# Proyecto_etapa_1_y_2.net
KiCad netlist of a schematic drawn in EAGLE
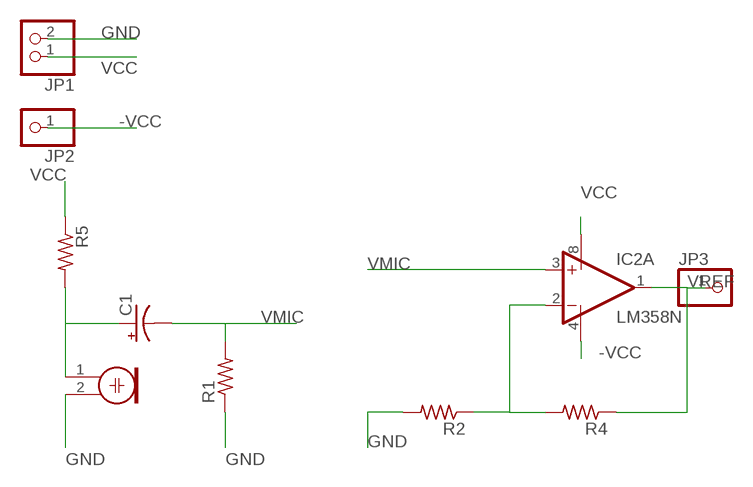
[diagram p0: schematic, sheet 1]

(export (version "E")
  (design (tool "Eeschema 10.0.6"))
  (components
    (comp (ref "C1")
      (value "CPOL-USE2.5-6")
      (footprint "eagle-import:E2,5-6")
      (libsource (lib "eagle-import") (part "CPOL-USE2.5-6"))
    )
    (comp (ref "IC2")
      (value "LM358N")
      (footprint "eagle-import:DIL08")
      (libsource (lib "eagle-import") (part "LM358N"))
    )
    (comp (ref "JP1")
      (value "PINHD-1X2")
      (footprint "eagle-import:1X02")
      (libsource (lib "eagle-import") (part "PINHD-1X2"))
    )
    (comp (ref "JP2")
      (value "PINHD-1X1")
      (footprint "eagle-import:1X01")
      (libsource (lib "eagle-import") (part "PINHD-1X1"))
    )
    (comp (ref "JP3")
      (value "PINHD-1X1")
      (footprint "eagle-import:1X01")
      (libsource (lib "eagle-import") (part "PINHD-1X1"))
    )
    (comp (ref "M2")
      (value "ELECTRET_MICROPHON-F6050AP")
      (footprint "eagle-import:F6050AP")
      (libsource (lib "eagle-import") (part "ELECTRET_MICROPHON-F6050AP"))
    )
    (comp (ref "R1")
      (value "R-US_0207/10")
      (footprint "eagle-import:0207_10")
      (libsource (lib "eagle-import") (part "R-US_0207/10"))
    )
    (comp (ref "R2")
      (value "R-US_0207/10")
      (footprint "eagle-import:0207_10")
      (libsource (lib "eagle-import") (part "R-US_0207/10"))
    )
    (comp (ref "R4")
      (value "R-US_0207/10")
      (footprint "eagle-import:0207_10")
      (libsource (lib "eagle-import") (part "R-US_0207/10"))
    )
    (comp (ref "R5")
      (value "R-US_0207/10")
      (footprint "eagle-import:0207_10")
      (libsource (lib "eagle-import") (part "R-US_0207/10"))
    )
  )
  (nets
    (net (code "1") (name "/-VCC") (class "Default")
      (node (ref "IC2") (pin "4") (pinfunction "V-_4") (pintype "power_in"))
      (node (ref "JP2") (pin "1") (pinfunction "1_1") (pintype "passive"))
    )
    (net (code "2") (name "/GND") (class "Default")
      (node (ref "JP1") (pin "2") (pinfunction "2_2") (pintype "passive"))
      (node (ref "M2") (pin "2") (pinfunction "2_2") (pintype "passive"))
      (node (ref "R1") (pin "1") (pinfunction "1_1") (pintype "passive"))
      (node (ref "R2") (pin "2") (pinfunction "2_2") (pintype "passive"))
    )
    (net (code "3") (name "/VCC") (class "Default")
      (node (ref "IC2") (pin "8") (pinfunction "V+_8") (pintype "power_in"))
      (node (ref "JP1") (pin "1") (pinfunction "1_1") (pintype "passive"))
      (node (ref "R5") (pin "1") (pinfunction "1_1") (pintype "passive"))
    )
    (net (code "4") (name "/VMIC") (class "Default")
      (node (ref "C1") (pin "-") (pinfunction "-_-") (pintype "passive"))
      (node (ref "IC2") (pin "3") (pinfunction "+IN_3") (pintype "input"))
      (node (ref "R1") (pin "2") (pinfunction "2_2") (pintype "passive"))
    )
    (net (code "5") (name "/VREF") (class "Default")
      (node (ref "IC2") (pin "1") (pinfunction "OUT_1") (pintype "output"))
      (node (ref "JP3") (pin "1") (pinfunction "1_1") (pintype "passive"))
      (node (ref "R4") (pin "1") (pinfunction "1_1") (pintype "passive"))
    )
    (net (code "6") (name "Net-(C1-Pad+)") (class "Default")
      (node (ref "C1") (pin "+") (pinfunction "+_+") (pintype "passive"))
      (node (ref "M2") (pin "1") (pinfunction "1_1") (pintype "passive"))
      (node (ref "R5") (pin "2") (pinfunction "2_2") (pintype "passive"))
    )
    (net (code "7") (name "Net-(IC2A--IN)") (class "Default")
      (node (ref "IC2") (pin "2") (pinfunction "-IN_2") (pintype "input"))
      (node (ref "R2") (pin "1") (pinfunction "1_1") (pintype "passive"))
      (node (ref "R4") (pin "2") (pinfunction "2_2") (pintype "passive"))
    )
  )
)
